# traintimes.net
KiCad netlist of a schematic drawn in EAGLE
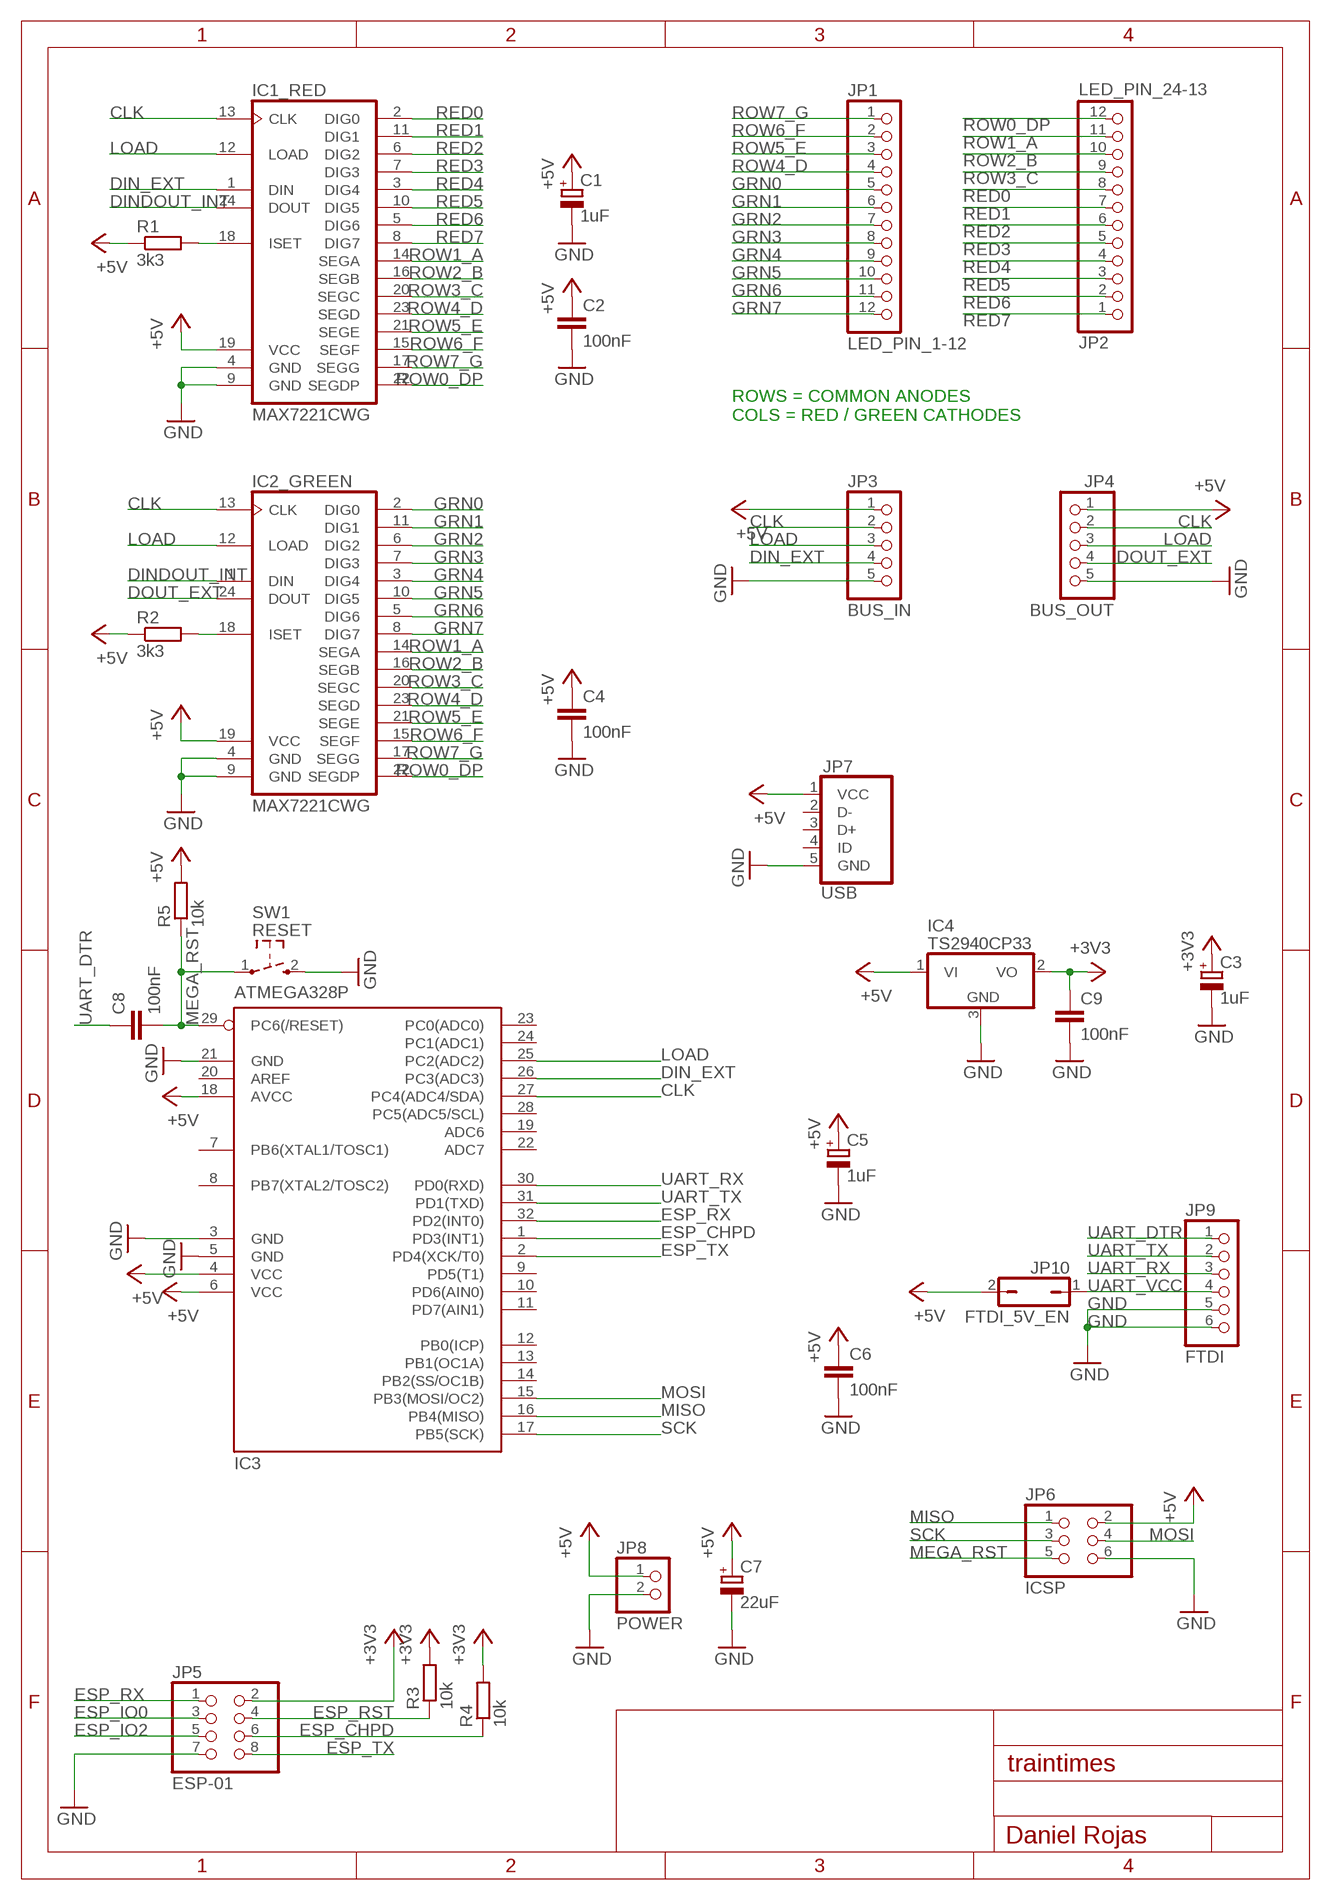
[diagram p0: schematic, sheet 1]

(export (version "E")
  (design (tool "Eeschema 10.0.6"))
  (components
    (comp (ref "C1")
      (value "1uF")
      (footprint "eagle-import:SMC_A")
      (libsource (lib "eagle-import") (part "CPOL-EUSMCA"))
    )
    (comp (ref "C2")
      (value "100nF")
      (footprint "eagle-import:C0805")
      (libsource (lib "eagle-import") (part "C-EUC0805"))
    )
    (comp (ref "C3")
      (value "1uF")
      (footprint "eagle-import:SMC_A")
      (libsource (lib "eagle-import") (part "CPOL-EUSMCA"))
    )
    (comp (ref "C4")
      (value "100nF")
      (footprint "eagle-import:C0805")
      (libsource (lib "eagle-import") (part "C-EUC0805"))
    )
    (comp (ref "C5")
      (value "1uF")
      (footprint "eagle-import:SMC_A")
      (libsource (lib "eagle-import") (part "CPOL-EUSMCA"))
    )
    (comp (ref "C6")
      (value "100nF")
      (footprint "eagle-import:C0805")
      (libsource (lib "eagle-import") (part "C-EUC0805"))
    )
    (comp (ref "C7")
      (value "22uF")
      (footprint "eagle-import:E2,5-6")
      (libsource (lib "eagle-import") (part "CPOL-EUE2.5-6"))
    )
    (comp (ref "C8")
      (value "100nF")
      (footprint "eagle-import:C0805")
      (libsource (lib "eagle-import") (part "C-EUC0805"))
    )
    (comp (ref "C9")
      (value "100nF")
      (footprint "eagle-import:C0805")
      (libsource (lib "eagle-import") (part "C-EUC0805"))
    )
    (comp (ref "IC1_RED")
      (value "MAX7221CWG")
      (footprint "eagle-import:SO24L")
      (libsource (lib "eagle-import") (part "MAX7219CWG"))
    )
    (comp (ref "IC2_GREEN")
      (value "MAX7221CWG")
      (footprint "eagle-import:SO24L")
      (libsource (lib "eagle-import") (part "MAX7219CWG"))
    )
    (comp (ref "IC3")
      (value "ATMEGA328P")
      (footprint "eagle-import:TQFP32-08")
      (fields (field (name "MPN") "ATMEGA8-16AU"))
      (libsource (lib "eagle-import") (part "MEGA8-AI"))
    )
    (comp (ref "IC4")
      (value "TS2940CP33")
      (footprint "eagle-import:TO252")
      (libsource (lib "eagle-import") (part "78DT05"))
    )
    (comp (ref "JP1")
      (value "LED_PIN_1-12")
      (footprint "eagle-import:1X12")
      (libsource (lib "eagle-import") (part "PINHD-1X12"))
    )
    (comp (ref "JP2")
      (value "LED_PIN_24-13")
      (footprint "eagle-import:1X12")
      (libsource (lib "eagle-import") (part "PINHD-1X12"))
    )
    (comp (ref "JP3")
      (value "BUS_IN")
      (footprint "eagle-import:1X05")
      (libsource (lib "eagle-import") (part "PINHD-1X5"))
    )
    (comp (ref "JP4")
      (value "BUS_OUT")
      (footprint "eagle-import:1X05")
      (libsource (lib "eagle-import") (part "PINHD-1X5"))
    )
    (comp (ref "JP5")
      (value "ESP-01")
      (footprint "eagle-import:2X04")
      (libsource (lib "eagle-import") (part "PINHD-2X4"))
    )
    (comp (ref "JP6")
      (value "ICSP")
      (footprint "eagle-import:2X03")
      (libsource (lib "eagle-import") (part "PINHD-2X3"))
    )
    (comp (ref "JP7")
      (value "USB")
      (footprint "eagle-import:FCI-10103594-0001LF")
      (libsource (lib "eagle-import") (part "USB-RECEPTABLE"))
    )
    (comp (ref "JP8")
      (value "POWER")
      (footprint "eagle-import:1X02")
      (libsource (lib "eagle-import") (part "PINHD-1X2"))
    )
    (comp (ref "JP9")
      (value "FTDI")
      (footprint "eagle-import:1X06")
      (libsource (lib "eagle-import") (part "PINHD-1X6"))
    )
    (comp (ref "JP10")
      (value "FTDI_5V_EN")
      (footprint "eagle-import:JP1")
      (libsource (lib "eagle-import") (part "JP1Q"))
    )
    (comp (ref "R1")
      (value "3k3")
      (footprint "eagle-import:R0805")
      (libsource (lib "eagle-import") (part "R-EU_R0805"))
    )
    (comp (ref "R2")
      (value "3k3")
      (footprint "eagle-import:R0805")
      (libsource (lib "eagle-import") (part "R-EU_R0805"))
    )
    (comp (ref "R3")
      (value "10k")
      (footprint "eagle-import:R0805")
      (libsource (lib "eagle-import") (part "R-EU_R0805"))
    )
    (comp (ref "R4")
      (value "10k")
      (footprint "eagle-import:R0805")
      (libsource (lib "eagle-import") (part "R-EU_R0805"))
    )
    (comp (ref "R5")
      (value "10k")
      (footprint "eagle-import:R0805")
      (libsource (lib "eagle-import") (part "R-EU_R0805"))
    )
    (comp (ref "SW1")
      (value "RESET")
      (footprint "eagle-import:SW_TACT_3X6")
      (libsource (lib "eagle-import") (part "SW_TACT_2P-3X6"))
    )
  )
  (nets
    (net (code "1") (name "+3V3") (class "Default")
      (node (ref "C3") (pin "+") (pinfunction "+_+") (pintype "passive"))
      (node (ref "C9") (pin "1") (pinfunction "1_1") (pintype "passive"))
      (node (ref "IC4") (pin "2") (pinfunction "VO_2") (pintype "passive"))
      (node (ref "JP5") (pin "2") (pinfunction "2_2") (pintype "passive"))
      (node (ref "R3") (pin "2") (pinfunction "2_2") (pintype "passive"))
      (node (ref "R4") (pin "2") (pinfunction "2_2") (pintype "passive"))
    )
    (net (code "2") (name "+5V") (class "Default")
      (node (ref "C1") (pin "+") (pinfunction "+_+") (pintype "passive"))
      (node (ref "C2") (pin "1") (pinfunction "1_1") (pintype "passive"))
      (node (ref "C4") (pin "1") (pinfunction "1_1") (pintype "passive"))
      (node (ref "C5") (pin "+") (pinfunction "+_+") (pintype "passive"))
      (node (ref "C6") (pin "1") (pinfunction "1_1") (pintype "passive"))
      (node (ref "C7") (pin "+") (pinfunction "+_+") (pintype "passive"))
      (node (ref "IC1_RED") (pin "19") (pinfunction "VCC_19") (pintype "power_in"))
      (node (ref "IC2_GREEN") (pin "19") (pinfunction "VCC_19") (pintype "power_in"))
      (node (ref "IC3") (pin "18") (pinfunction "AVCC_18") (pintype "power_in"))
      (node (ref "IC3") (pin "4") (pinfunction "VCC_4") (pintype "power_in"))
      (node (ref "IC3") (pin "6") (pinfunction "VCC_6") (pintype "power_in"))
      (node (ref "IC4") (pin "1") (pinfunction "VI_1") (pintype "input"))
      (node (ref "JP10") (pin "2") (pinfunction "2_2") (pintype "passive"))
      (node (ref "JP3") (pin "1") (pinfunction "1_1") (pintype "passive"))
      (node (ref "JP4") (pin "1") (pinfunction "1_1") (pintype "passive"))
      (node (ref "JP6") (pin "2") (pinfunction "2_2") (pintype "passive"))
      (node (ref "JP7") (pin "1") (pinfunction "VCC_1") (pintype "bidirectional"))
      (node (ref "JP8") (pin "1") (pinfunction "1_1") (pintype "passive"))
      (node (ref "R1") (pin "1") (pinfunction "1_1") (pintype "passive"))
      (node (ref "R2") (pin "1") (pinfunction "1_1") (pintype "passive"))
      (node (ref "R5") (pin "2") (pinfunction "2_2") (pintype "passive"))
    )
    (net (code "3") (name "/CLK") (class "Default")
      (node (ref "IC1_RED") (pin "13") (pinfunction "CLK_13") (pintype "input"))
      (node (ref "IC2_GREEN") (pin "13") (pinfunction "CLK_13") (pintype "input"))
      (node (ref "IC3") (pin "27") (pinfunction "PC4(ADC4/SDA)_27") (pintype "bidirectional"))
      (node (ref "JP3") (pin "2") (pinfunction "2_2") (pintype "passive"))
      (node (ref "JP4") (pin "2") (pinfunction "2_2") (pintype "passive"))
    )
    (net (code "4") (name "/DINDOUT_INT") (class "Default")
      (node (ref "IC1_RED") (pin "24") (pinfunction "DOUT_24") (pintype "output"))
      (node (ref "IC2_GREEN") (pin "1") (pinfunction "DIN_1") (pintype "input"))
    )
    (net (code "5") (name "/DIN_EXT") (class "Default")
      (node (ref "IC1_RED") (pin "1") (pinfunction "DIN_1") (pintype "input"))
      (node (ref "IC3") (pin "26") (pinfunction "PC3(ADC3)_26") (pintype "bidirectional"))
      (node (ref "JP3") (pin "4") (pinfunction "4_4") (pintype "passive"))
    )
    (net (code "6") (name "/DOUT_EXT") (class "Default")
      (node (ref "IC2_GREEN") (pin "24") (pinfunction "DOUT_24") (pintype "output"))
      (node (ref "JP4") (pin "4") (pinfunction "4_4") (pintype "passive"))
    )
    (net (code "7") (name "/ESP_CHPD") (class "Default")
      (node (ref "IC3") (pin "1") (pinfunction "PD3(INT1)_1") (pintype "bidirectional"))
      (node (ref "JP5") (pin "6") (pinfunction "6_6") (pintype "passive"))
      (node (ref "R4") (pin "1") (pinfunction "1_1") (pintype "passive"))
    )
    (net (code "8") (name "/ESP_IO0") (class "Default")
      (node (ref "JP5") (pin "3") (pinfunction "3_3") (pintype "passive"))
    )
    (net (code "9") (name "/ESP_IO2") (class "Default")
      (node (ref "JP5") (pin "5") (pinfunction "5_5") (pintype "passive"))
    )
    (net (code "10") (name "/ESP_RST") (class "Default")
      (node (ref "JP5") (pin "4") (pinfunction "4_4") (pintype "passive"))
      (node (ref "R3") (pin "1") (pinfunction "1_1") (pintype "passive"))
    )
    (net (code "11") (name "/ESP_RX") (class "Default")
      (node (ref "IC3") (pin "32") (pinfunction "PD2(INT0)_32") (pintype "bidirectional"))
      (node (ref "JP5") (pin "1") (pinfunction "1_1") (pintype "passive"))
    )
    (net (code "12") (name "/ESP_TX") (class "Default")
      (node (ref "IC3") (pin "2") (pinfunction "PD4(XCK/T0)_2") (pintype "bidirectional"))
      (node (ref "JP5") (pin "8") (pinfunction "8_8") (pintype "passive"))
    )
    (net (code "13") (name "/GRN0") (class "Default")
      (node (ref "IC2_GREEN") (pin "2") (pinfunction "DIG0_2") (pintype "output"))
      (node (ref "JP1") (pin "5") (pinfunction "5_5") (pintype "passive"))
    )
    (net (code "14") (name "/GRN1") (class "Default")
      (node (ref "IC2_GREEN") (pin "11") (pinfunction "DIG1_11") (pintype "output"))
      (node (ref "JP1") (pin "6") (pinfunction "6_6") (pintype "passive"))
    )
    (net (code "15") (name "/GRN2") (class "Default")
      (node (ref "IC2_GREEN") (pin "6") (pinfunction "DIG2_6") (pintype "output"))
      (node (ref "JP1") (pin "7") (pinfunction "7_7") (pintype "passive"))
    )
    (net (code "16") (name "/GRN3") (class "Default")
      (node (ref "IC2_GREEN") (pin "7") (pinfunction "DIG3_7") (pintype "output"))
      (node (ref "JP1") (pin "8") (pinfunction "8_8") (pintype "passive"))
    )
    (net (code "17") (name "/GRN4") (class "Default")
      (node (ref "IC2_GREEN") (pin "3") (pinfunction "DIG4_3") (pintype "output"))
      (node (ref "JP1") (pin "9") (pinfunction "9_9") (pintype "passive"))
    )
    (net (code "18") (name "/GRN5") (class "Default")
      (node (ref "IC2_GREEN") (pin "10") (pinfunction "DIG5_10") (pintype "output"))
      (node (ref "JP1") (pin "10") (pinfunction "10_10") (pintype "passive"))
    )
    (net (code "19") (name "/GRN6") (class "Default")
      (node (ref "IC2_GREEN") (pin "5") (pinfunction "DIG6_5") (pintype "output"))
      (node (ref "JP1") (pin "11") (pinfunction "11_11") (pintype "passive"))
    )
    (net (code "20") (name "/GRN7") (class "Default")
      (node (ref "IC2_GREEN") (pin "8") (pinfunction "DIG7_8") (pintype "output"))
      (node (ref "JP1") (pin "12") (pinfunction "12_12") (pintype "passive"))
    )
    (net (code "21") (name "/LOAD") (class "Default")
      (node (ref "IC1_RED") (pin "12") (pinfunction "LOAD_12") (pintype "input"))
      (node (ref "IC2_GREEN") (pin "12") (pinfunction "LOAD_12") (pintype "input"))
      (node (ref "IC3") (pin "25") (pinfunction "PC2(ADC2)_25") (pintype "bidirectional"))
      (node (ref "JP3") (pin "3") (pinfunction "3_3") (pintype "passive"))
      (node (ref "JP4") (pin "3") (pinfunction "3_3") (pintype "passive"))
    )
    (net (code "22") (name "/MEGA_RST") (class "Default")
      (node (ref "C8") (pin "2") (pinfunction "2_2") (pintype "passive"))
      (node (ref "IC3") (pin "29") (pinfunction "PC6(/RESET)_29") (pintype "bidirectional"))
      (node (ref "JP6") (pin "5") (pinfunction "5_5") (pintype "passive"))
      (node (ref "R5") (pin "1") (pinfunction "1_1") (pintype "passive"))
      (node (ref "SW1") (pin "1") (pinfunction "1_1") (pintype "passive"))
    )
    (net (code "23") (name "/MISO") (class "Default")
      (node (ref "IC3") (pin "16") (pinfunction "PB4(MISO)_16") (pintype "bidirectional"))
      (node (ref "JP6") (pin "1") (pinfunction "1_1") (pintype "passive"))
    )
    (net (code "24") (name "/MOSI") (class "Default")
      (node (ref "IC3") (pin "15") (pinfunction "PB3(MOSI/OC2)_15") (pintype "bidirectional"))
      (node (ref "JP6") (pin "4") (pinfunction "4_4") (pintype "passive"))
    )
    (net (code "25") (name "/RED0") (class "Default")
      (node (ref "IC1_RED") (pin "2") (pinfunction "DIG0_2") (pintype "output"))
      (node (ref "JP2") (pin "8") (pinfunction "8_8") (pintype "passive"))
    )
    (net (code "26") (name "/RED1") (class "Default")
      (node (ref "IC1_RED") (pin "11") (pinfunction "DIG1_11") (pintype "output"))
      (node (ref "JP2") (pin "7") (pinfunction "7_7") (pintype "passive"))
    )
    (net (code "27") (name "/RED2") (class "Default")
      (node (ref "IC1_RED") (pin "6") (pinfunction "DIG2_6") (pintype "output"))
      (node (ref "JP2") (pin "6") (pinfunction "6_6") (pintype "passive"))
    )
    (net (code "28") (name "/RED3") (class "Default")
      (node (ref "IC1_RED") (pin "7") (pinfunction "DIG3_7") (pintype "output"))
      (node (ref "JP2") (pin "5") (pinfunction "5_5") (pintype "passive"))
    )
    (net (code "29") (name "/RED4") (class "Default")
      (node (ref "IC1_RED") (pin "3") (pinfunction "DIG4_3") (pintype "output"))
      (node (ref "JP2") (pin "4") (pinfunction "4_4") (pintype "passive"))
    )
    (net (code "30") (name "/RED5") (class "Default")
      (node (ref "IC1_RED") (pin "10") (pinfunction "DIG5_10") (pintype "output"))
      (node (ref "JP2") (pin "3") (pinfunction "3_3") (pintype "passive"))
    )
    (net (code "31") (name "/RED6") (class "Default")
      (node (ref "IC1_RED") (pin "5") (pinfunction "DIG6_5") (pintype "output"))
      (node (ref "JP2") (pin "2") (pinfunction "2_2") (pintype "passive"))
    )
    (net (code "32") (name "/RED7") (class "Default")
      (node (ref "IC1_RED") (pin "8") (pinfunction "DIG7_8") (pintype "output"))
      (node (ref "JP2") (pin "1") (pinfunction "1_1") (pintype "passive"))
    )
    (net (code "33") (name "/ROW0_DP") (class "Default")
      (node (ref "IC1_RED") (pin "22") (pinfunction "SEGDP_22") (pintype "output"))
      (node (ref "IC2_GREEN") (pin "22") (pinfunction "SEGDP_22") (pintype "output"))
      (node (ref "JP2") (pin "12") (pinfunction "12_12") (pintype "passive"))
    )
    (net (code "34") (name "/ROW1_A") (class "Default")
      (node (ref "IC1_RED") (pin "14") (pinfunction "SEGA_14") (pintype "output"))
      (node (ref "IC2_GREEN") (pin "14") (pinfunction "SEGA_14") (pintype "output"))
      (node (ref "JP2") (pin "11") (pinfunction "11_11") (pintype "passive"))
    )
    (net (code "35") (name "/ROW2_B") (class "Default")
      (node (ref "IC1_RED") (pin "16") (pinfunction "SEGB_16") (pintype "output"))
      (node (ref "IC2_GREEN") (pin "16") (pinfunction "SEGB_16") (pintype "output"))
      (node (ref "JP2") (pin "10") (pinfunction "10_10") (pintype "passive"))
    )
    (net (code "36") (name "/ROW3_C") (class "Default")
      (node (ref "IC1_RED") (pin "20") (pinfunction "SEGC_20") (pintype "output"))
      (node (ref "IC2_GREEN") (pin "20") (pinfunction "SEGC_20") (pintype "output"))
      (node (ref "JP2") (pin "9") (pinfunction "9_9") (pintype "passive"))
    )
    (net (code "37") (name "/ROW4_D") (class "Default")
      (node (ref "IC1_RED") (pin "23") (pinfunction "SEGD_23") (pintype "output"))
      (node (ref "IC2_GREEN") (pin "23") (pinfunction "SEGD_23") (pintype "output"))
      (node (ref "JP1") (pin "4") (pinfunction "4_4") (pintype "passive"))
    )
    (net (code "38") (name "/ROW5_E") (class "Default")
      (node (ref "IC1_RED") (pin "21") (pinfunction "SEGE_21") (pintype "output"))
      (node (ref "IC2_GREEN") (pin "21") (pinfunction "SEGE_21") (pintype "output"))
      (node (ref "JP1") (pin "3") (pinfunction "3_3") (pintype "passive"))
    )
    (net (code "39") (name "/ROW6_F") (class "Default")
      (node (ref "IC1_RED") (pin "15") (pinfunction "SEGF_15") (pintype "output"))
      (node (ref "IC2_GREEN") (pin "15") (pinfunction "SEGF_15") (pintype "output"))
      (node (ref "JP1") (pin "2") (pinfunction "2_2") (pintype "passive"))
    )
    (net (code "40") (name "/ROW7_G") (class "Default")
      (node (ref "IC1_RED") (pin "17") (pinfunction "SEGG_17") (pintype "output"))
      (node (ref "IC2_GREEN") (pin "17") (pinfunction "SEGG_17") (pintype "output"))
      (node (ref "JP1") (pin "1") (pinfunction "1_1") (pintype "passive"))
    )
    (net (code "41") (name "/SCK") (class "Default")
      (node (ref "IC3") (pin "17") (pinfunction "PB5(SCK)_17") (pintype "bidirectional"))
      (node (ref "JP6") (pin "3") (pinfunction "3_3") (pintype "passive"))
    )
    (net (code "42") (name "/UART_DTR") (class "Default")
      (node (ref "C8") (pin "1") (pinfunction "1_1") (pintype "passive"))
      (node (ref "JP9") (pin "1") (pinfunction "1_1") (pintype "passive"))
    )
    (net (code "43") (name "/UART_RX") (class "Default")
      (node (ref "IC3") (pin "30") (pinfunction "PD0(RXD)_30") (pintype "bidirectional"))
      (node (ref "JP9") (pin "3") (pinfunction "3_3") (pintype "passive"))
    )
    (net (code "44") (name "/UART_TX") (class "Default")
      (node (ref "IC3") (pin "31") (pinfunction "PD1(TXD)_31") (pintype "bidirectional"))
      (node (ref "JP9") (pin "2") (pinfunction "2_2") (pintype "passive"))
    )
    (net (code "45") (name "/UART_VCC") (class "Default")
      (node (ref "JP10") (pin "1") (pinfunction "1_1") (pintype "passive"))
      (node (ref "JP9") (pin "4") (pinfunction "4_4") (pintype "passive"))
    )
    (net (code "46") (name "GND") (class "Default")
      (node (ref "C1") (pin "-") (pinfunction "-_-") (pintype "passive"))
      (node (ref "C2") (pin "2") (pinfunction "2_2") (pintype "passive"))
      (node (ref "C3") (pin "-") (pinfunction "-_-") (pintype "passive"))
      (node (ref "C4") (pin "2") (pinfunction "2_2") (pintype "passive"))
      (node (ref "C5") (pin "-") (pinfunction "-_-") (pintype "passive"))
      (node (ref "C6") (pin "2") (pinfunction "2_2") (pintype "passive"))
      (node (ref "C7") (pin "-") (pinfunction "-_-") (pintype "passive"))
      (node (ref "C9") (pin "2") (pinfunction "2_2") (pintype "passive"))
      (node (ref "IC1_RED") (pin "4") (pinfunction "GND_4") (pintype "power_in"))
      (node (ref "IC1_RED") (pin "9") (pinfunction "GND_9") (pintype "power_in"))
      (node (ref "IC2_GREEN") (pin "4") (pinfunction "GND_4") (pintype "power_in"))
      (node (ref "IC2_GREEN") (pin "9") (pinfunction "GND_9") (pintype "power_in"))
      (node (ref "IC3") (pin "21") (pinfunction "GND_21") (pintype "power_in"))
      (node (ref "IC3") (pin "3") (pinfunction "GND_3") (pintype "power_in"))
      (node (ref "IC3") (pin "5") (pinfunction "GND_5") (pintype "power_in"))
      (node (ref "IC4") (pin "3") (pinfunction "GND_3") (pintype "passive"))
      (node (ref "JP3") (pin "5") (pinfunction "5_5") (pintype "passive"))
      (node (ref "JP4") (pin "5") (pinfunction "5_5") (pintype "passive"))
      (node (ref "JP5") (pin "7") (pinfunction "7_7") (pintype "passive"))
      (node (ref "JP6") (pin "6") (pinfunction "6_6") (pintype "passive"))
      (node (ref "JP7") (pin "5") (pinfunction "GND_5") (pintype "bidirectional"))
      (node (ref "JP8") (pin "2") (pinfunction "2_2") (pintype "passive"))
      (node (ref "JP9") (pin "5") (pinfunction "5_5") (pintype "passive"))
      (node (ref "JP9") (pin "6") (pinfunction "6_6") (pintype "passive"))
      (node (ref "SW1") (pin "2") (pinfunction "3_2") (pintype "passive"))
    )
    (net (code "47") (name "Net-(IC1_RED-ISET)") (class "Default")
      (node (ref "IC1_RED") (pin "18") (pinfunction "ISET_18") (pintype "input"))
      (node (ref "R1") (pin "2") (pinfunction "2_2") (pintype "passive"))
    )
    (net (code "48") (name "Net-(IC2_GREEN-ISET)") (class "Default")
      (node (ref "IC2_GREEN") (pin "18") (pinfunction "ISET_18") (pintype "input"))
      (node (ref "R2") (pin "2") (pinfunction "2_2") (pintype "passive"))
    )
    (net (code "49") (name "unconnected-(IC3-ADC6-Pad19)") (class "Default")
      (node (ref "IC3") (pin "19") (pinfunction "ADC6_19") (pintype "bidirectional"))
    )
    (net (code "50") (name "unconnected-(IC3-ADC7-Pad22)") (class "Default")
      (node (ref "IC3") (pin "22") (pinfunction "ADC7_22") (pintype "bidirectional"))
    )
    (net (code "51") (name "unconnected-(IC3-AREF-Pad20)") (class "Default")
      (node (ref "IC3") (pin "20") (pinfunction "AREF_20") (pintype "passive"))
    )
    (net (code "52") (name "unconnected-(IC3-PB0(ICP)-Pad12)") (class "Default")
      (node (ref "IC3") (pin "12") (pinfunction "PB0(ICP)_12") (pintype "bidirectional"))
    )
    (net (code "53") (name "unconnected-(IC3-PB1(OC1A)-Pad13)") (class "Default")
      (node (ref "IC3") (pin "13") (pinfunction "PB1(OC1A)_13") (pintype "bidirectional"))
    )
    (net (code "54") (name "unconnected-(IC3-PB2(SS{slash}OC1B)-Pad14)") (class "Default")
      (node (ref "IC3") (pin "14") (pinfunction "PB2(SS/OC1B)_14") (pintype "bidirectional"))
    )
    (net (code "55") (name "unconnected-(IC3-PB6(XTAL1{slash}TOSC1)-Pad7)") (class "Default")
      (node (ref "IC3") (pin "7") (pinfunction "PB6(XTAL1/TOSC1)_7") (pintype "bidirectional"))
    )
    (net (code "56") (name "unconnected-(IC3-PB7(XTAL2{slash}TOSC2)-Pad8)") (class "Default")
      (node (ref "IC3") (pin "8") (pinfunction "PB7(XTAL2/TOSC2)_8") (pintype "bidirectional"))
    )
    (net (code "57") (name "unconnected-(IC3-PC0(ADC0)-Pad23)") (class "Default")
      (node (ref "IC3") (pin "23") (pinfunction "PC0(ADC0)_23") (pintype "bidirectional"))
    )
    (net (code "58") (name "unconnected-(IC3-PC1(ADC1)-Pad24)") (class "Default")
      (node (ref "IC3") (pin "24") (pinfunction "PC1(ADC1)_24") (pintype "bidirectional"))
    )
    (net (code "59") (name "unconnected-(IC3-PC5(ADC5{slash}SCL)-Pad28)") (class "Default")
      (node (ref "IC3") (pin "28") (pinfunction "PC5(ADC5/SCL)_28") (pintype "bidirectional"))
    )
    (net (code "60") (name "unconnected-(IC3-PD5(T1)-Pad9)") (class "Default")
      (node (ref "IC3") (pin "9") (pinfunction "PD5(T1)_9") (pintype "bidirectional"))
    )
    (net (code "61") (name "unconnected-(IC3-PD6(AIN0)-Pad10)") (class "Default")
      (node (ref "IC3") (pin "10") (pinfunction "PD6(AIN0)_10") (pintype "bidirectional"))
    )
    (net (code "62") (name "unconnected-(IC3-PD7(AIN1)-Pad11)") (class "Default")
      (node (ref "IC3") (pin "11") (pinfunction "PD7(AIN1)_11") (pintype "bidirectional"))
    )
    (net (code "63") (name "unconnected-(JP7-D+-Pad3)") (class "Default")
      (node (ref "JP7") (pin "3") (pinfunction "D+_3") (pintype "bidirectional"))
    )
    (net (code "64") (name "unconnected-(JP7-D--Pad2)") (class "Default")
      (node (ref "JP7") (pin "2") (pinfunction "D-_2") (pintype "bidirectional"))
    )
    (net (code "65") (name "unconnected-(JP7-ID-Pad4)") (class "Default")
      (node (ref "JP7") (pin "4") (pinfunction "ID_4") (pintype "bidirectional"))
    )
  )
)
